# Ethernet_PHY.net
KiCad netlist of a schematic drawn in Altium Designer
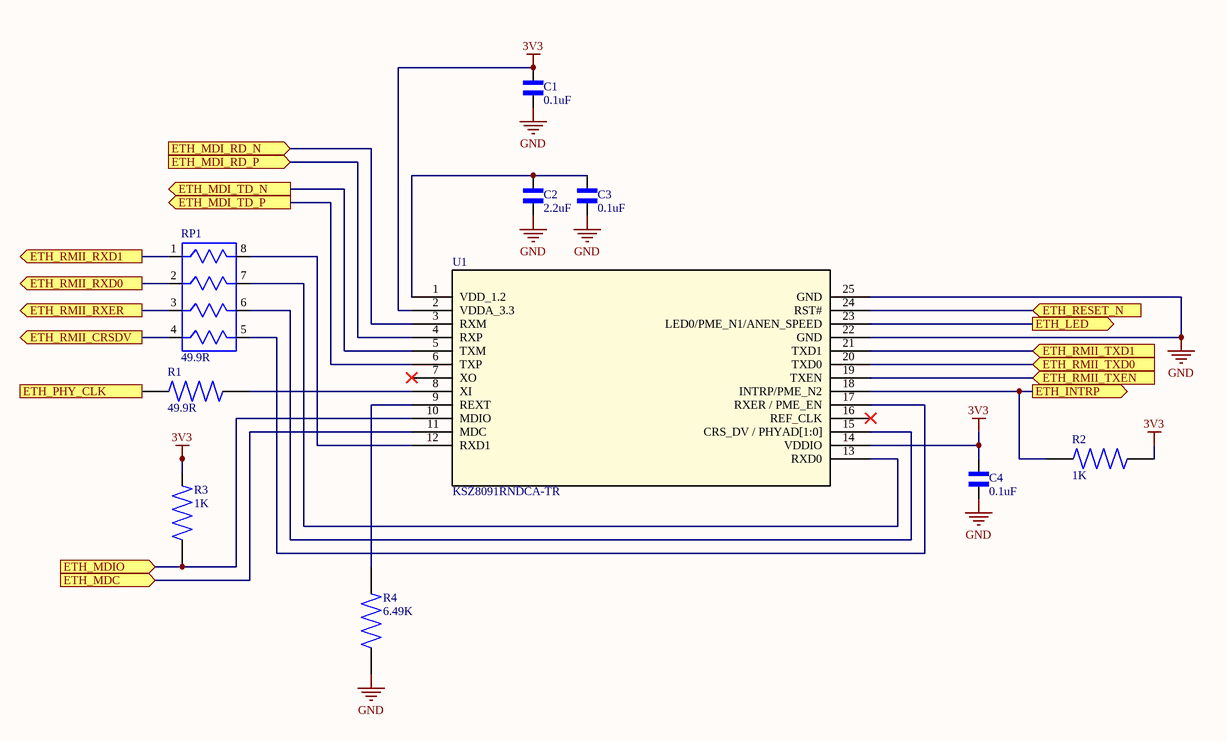
[diagram p0: Ethernet_PHY.SchDoc]

(export (version "E")
  (design (tool "Eeschema 10.0.6"))
  (components
    (comp (ref "C1")
      (value "0.1uF")
      (footprint "C0402")
      (description "CAP CER 0.1UF 6.3V X5R 01005")
      (fields
        (field (name "MANUFACTURER") "Murata")
        (field (name "MANUFACTURER PART NUMBER") "GRM022R60J104KE15L")
      )
      (libsource (lib "nnts") (part "GRM022R60J104KE15L"))
    )
    (comp (ref "C2")
      (value "2.2uF")
      (footprint "C0603")
      (description "Cap Ceramic 2.2uF 10V X5R 10% Pad SMD 0603 85C T/R")
      (fields
        (field (name "MANUFACTURER") "Taiyo Yuden")
        (field (name "MANUFACTURER PART NUMBER") "LMK107BJ225KK-T")
      )
      (libsource (lib "nnts") (part "LMK107BJ225KK-T"))
    )
    (comp (ref "C3")
      (value "0.1uF")
      (footprint "C0402")
      (description "CAP CER 0.1UF 6.3V X5R 01005")
      (fields
        (field (name "MANUFACTURER") "Murata")
        (field (name "MANUFACTURER PART NUMBER") "GRM022R60J104KE15L")
      )
      (libsource (lib "nnts") (part "GRM022R60J104KE15L"))
    )
    (comp (ref "C4")
      (value "0.1uF")
      (footprint "C0402")
      (description "CAP CER 0.1UF 6.3V X5R 01005")
      (fields
        (field (name "MANUFACTURER") "Murata")
        (field (name "MANUFACTURER PART NUMBER") "GRM022R60J104KE15L")
      )
      (libsource (lib "nnts") (part "GRM022R60J104KE15L"))
    )
    (comp (ref "R1")
      (value "49.9R")
      (footprint "R0402 Vishay")
      (description "RES SMD 49.9 OHM 1% 1/16W 0402")
      (fields
        (field (name "MANUFACTURER") "Vishay")
        (field (name "MANUFACTURER PART NUMBER") "CRCW040249R9FKTD")
      )
      (libsource (lib "nnts") (part "CRCW040249R9FKTD"))
    )
    (comp (ref "R2")
      (value "1K")
      (footprint "R0603 Vishay")
      (description "Res Thick Film 0201 1K Ohm 1% 1/20W 200ppm/C Molded SMD SMD Paper T/R")
      (fields
        (field (name "MANUFACTURER") "Vishay")
        (field (name "MANUFACTURER PART NUMBER") "CRCW02011K00FNED")
      )
      (libsource (lib "nnts") (part "CRCW02011K00FNED"))
    )
    (comp (ref "R3")
      (value "1K")
      (footprint "R0603 Vishay")
      (description "Res Thick Film 0201 1K Ohm 1% 1/20W 200ppm/C Molded SMD SMD Paper T/R")
      (fields
        (field (name "MANUFACTURER") "Vishay")
        (field (name "MANUFACTURER PART NUMBER") "CRCW02011K00FNED")
      )
      (libsource (lib "nnts") (part "CRCW02011K00FNED"))
    )
    (comp (ref "R4")
      (value "6.49K")
      (footprint "R0603 Vishay")
      (description "RES SMD 6.49K OHM 1% 1/20W 0201")
      (fields
        (field (name "MANUFACTURER") "Vishay")
        (field (name "MANUFACTURER PART NUMBER") "CRCW02016K49FNED")
      )
      (libsource (lib "nnts") (part "CRCW02016K49FNED"))
    )
    (comp (ref "RP1")
      (value "49.9R")
      (footprint "RESCAXS50P200X100X55-8N")
      (description "Res Thick Film Array 49.9 Ohm 1% 200ppm/C ISOL Molded 8-Pin 0804(4 X 0402) Convex SMD Paper T/R")
      (fields
        (field (name "MANUFACTURER") "Yageo")
        (field (name "MANUFACTURER PART NUMBER") "YC124-FR-0749R9L")
      )
      (libsource (lib "nnts") (part "YC124-FR-0749R9L"))
    )
    (comp (ref "U1")
      (value "KSZ8091RNDCA-TR")
      (footprint "QFN50P400X400X90-25N")
      (description "10/100 Base-Tx Physical Layer Transceiver, Eee, Wol / 24 Vqfn 4X4X0.9Mm T/r")
      (fields (field (name "COPYRIGHT") "Copyright (C) 2018 Accelerated Designs. All rights reserved"))
      (libsource (lib "nnts") (part "KSZ8091RNDCA-TR"))
    )
  )
  (nets
    (net (code "1") (name "/ETH_INTRP") (class "Default")
      (node (ref "R2") (pin "2") (pinfunction "2_2") (pintype "passive"))
      (node (ref "U1") (pin "18") (pinfunction "INTRP/PME_N2_18") (pintype "passive"))
    )
    (net (code "2") (name "/ETH_LED") (class "Default")
      (node (ref "U1") (pin "23") (pinfunction "LED0/PME_N1/ANEN_SPEED_23") (pintype "passive"))
    )
    (net (code "3") (name "/ETH_MDC") (class "Default")
      (node (ref "U1") (pin "11") (pinfunction "MDC_11") (pintype "passive"))
    )
    (net (code "4") (name "/ETH_MDIO") (class "Default")
      (node (ref "R3") (pin "1") (pinfunction "1_1") (pintype "passive"))
      (node (ref "U1") (pin "10") (pinfunction "MDIO_10") (pintype "passive"))
    )
    (net (code "5") (name "/ETH_MDI_RD_N") (class "Default")
      (node (ref "U1") (pin "3") (pinfunction "RXM_3") (pintype "passive"))
    )
    (net (code "6") (name "/ETH_MDI_RD_P") (class "Default")
      (node (ref "U1") (pin "4") (pinfunction "RXP_4") (pintype "passive"))
    )
    (net (code "7") (name "/ETH_MDI_TD_N") (class "Default")
      (node (ref "U1") (pin "5") (pinfunction "TXM_5") (pintype "passive"))
    )
    (net (code "8") (name "/ETH_MDI_TD_P") (class "Default")
      (node (ref "U1") (pin "6") (pinfunction "TXP_6") (pintype "passive"))
    )
    (net (code "9") (name "/ETH_PHY_CLK") (class "Default")
      (node (ref "R1") (pin "1") (pinfunction "1_1") (pintype "passive"))
    )
    (net (code "10") (name "/ETH_RESET_N") (class "Default")
      (node (ref "U1") (pin "24") (pinfunction "RST#_24") (pintype "passive"))
    )
    (net (code "11") (name "/ETH_RMII_CRSDV") (class "Default")
      (node (ref "RP1") (pin "4") (pinfunction "4_4") (pintype "passive"))
    )
    (net (code "12") (name "/ETH_RMII_RXD0") (class "Default")
      (node (ref "RP1") (pin "2") (pinfunction "2_2") (pintype "passive"))
    )
    (net (code "13") (name "/ETH_RMII_RXD1") (class "Default")
      (node (ref "RP1") (pin "1") (pinfunction "1_1") (pintype "passive"))
    )
    (net (code "14") (name "/ETH_RMII_RXER") (class "Default")
      (node (ref "RP1") (pin "3") (pinfunction "3_3") (pintype "passive"))
    )
    (net (code "15") (name "/ETH_RMII_TXD0") (class "Default")
      (node (ref "U1") (pin "20") (pinfunction "TXD0_20") (pintype "passive"))
    )
    (net (code "16") (name "/ETH_RMII_TXD1") (class "Default")
      (node (ref "U1") (pin "21") (pinfunction "TXD1_21") (pintype "passive"))
    )
    (net (code "17") (name "/ETH_RMII_TXEN") (class "Default")
      (node (ref "U1") (pin "19") (pinfunction "TXEN_19") (pintype "passive"))
    )
    (net (code "18") (name "3V3") (class "Default")
      (node (ref "C1") (pin "2") (pinfunction "2_2") (pintype "passive"))
      (node (ref "C4") (pin "2") (pinfunction "2_2") (pintype "passive"))
      (node (ref "R2") (pin "1") (pinfunction "1_1") (pintype "passive"))
      (node (ref "R3") (pin "2") (pinfunction "2_2") (pintype "passive"))
      (node (ref "U1") (pin "14") (pinfunction "VDDIO_14") (pintype "power_in"))
      (node (ref "U1") (pin "2") (pinfunction "VDDA_3.3_2") (pintype "power_in"))
    )
    (net (code "19") (name "GND") (class "Default")
      (node (ref "C1") (pin "1") (pinfunction "1_1") (pintype "passive"))
      (node (ref "C2") (pin "1") (pinfunction "1_1") (pintype "passive"))
      (node (ref "C3") (pin "1") (pinfunction "1_1") (pintype "passive"))
      (node (ref "C4") (pin "1") (pinfunction "1_1") (pintype "passive"))
      (node (ref "R4") (pin "1") (pinfunction "1_1") (pintype "passive"))
      (node (ref "U1") (pin "22") (pinfunction "GND_22") (pintype "passive"))
      (node (ref "U1") (pin "25") (pinfunction "GND_25") (pintype "passive"))
    )
    (net (code "20") (name "Net-(U1-CRS_DV_{slash}_PHYAD[1:0])") (class "Default")
      (node (ref "RP1") (pin "6") (pinfunction "6_6") (pintype "passive"))
      (node (ref "U1") (pin "15") (pinfunction "CRS_DV_/_PHYAD[1:0]_15") (pintype "passive"))
    )
    (net (code "21") (name "Net-(U1-REXT)") (class "Default")
      (node (ref "R4") (pin "2") (pinfunction "2_2") (pintype "passive"))
      (node (ref "U1") (pin "9") (pinfunction "REXT_9") (pintype "passive"))
    )
    (net (code "22") (name "Net-(U1-RXD0)") (class "Default")
      (node (ref "RP1") (pin "7") (pinfunction "7_7") (pintype "passive"))
      (node (ref "U1") (pin "13") (pinfunction "RXD0_13") (pintype "passive"))
    )
    (net (code "23") (name "Net-(U1-RXD1)") (class "Default")
      (node (ref "RP1") (pin "8") (pinfunction "8_8") (pintype "passive"))
      (node (ref "U1") (pin "12") (pinfunction "RXD1_12") (pintype "passive"))
    )
    (net (code "24") (name "Net-(U1-RXER_{slash}_PME_EN)") (class "Default")
      (node (ref "RP1") (pin "5") (pinfunction "5_5") (pintype "passive"))
      (node (ref "U1") (pin "17") (pinfunction "RXER_/_PME_EN_17") (pintype "passive"))
    )
    (net (code "25") (name "Net-(U1-VDD_1.2)") (class "Default")
      (node (ref "C2") (pin "2") (pinfunction "2_2") (pintype "passive"))
      (node (ref "C3") (pin "2") (pinfunction "2_2") (pintype "passive"))
      (node (ref "U1") (pin "1") (pinfunction "VDD_1.2_1") (pintype "power_in"))
    )
    (net (code "26") (name "Net-(U1-XI)") (class "Default")
      (node (ref "R1") (pin "2") (pinfunction "2_2") (pintype "passive"))
      (node (ref "U1") (pin "8") (pinfunction "XI_8") (pintype "passive"))
    )
    (net (code "27") (name "unconnected-(U1-REF_CLK-Pad16)") (class "Default")
      (node (ref "U1") (pin "16") (pinfunction "REF_CLK_16") (pintype "passive+no_connect"))
    )
    (net (code "28") (name "unconnected-(U1-XO-Pad7)") (class "Default")
      (node (ref "U1") (pin "7") (pinfunction "XO_7") (pintype "passive+no_connect"))
    )
  )
)
